# ALU_Adder.net
KiCad netlist of a schematic drawn in Altium Designer
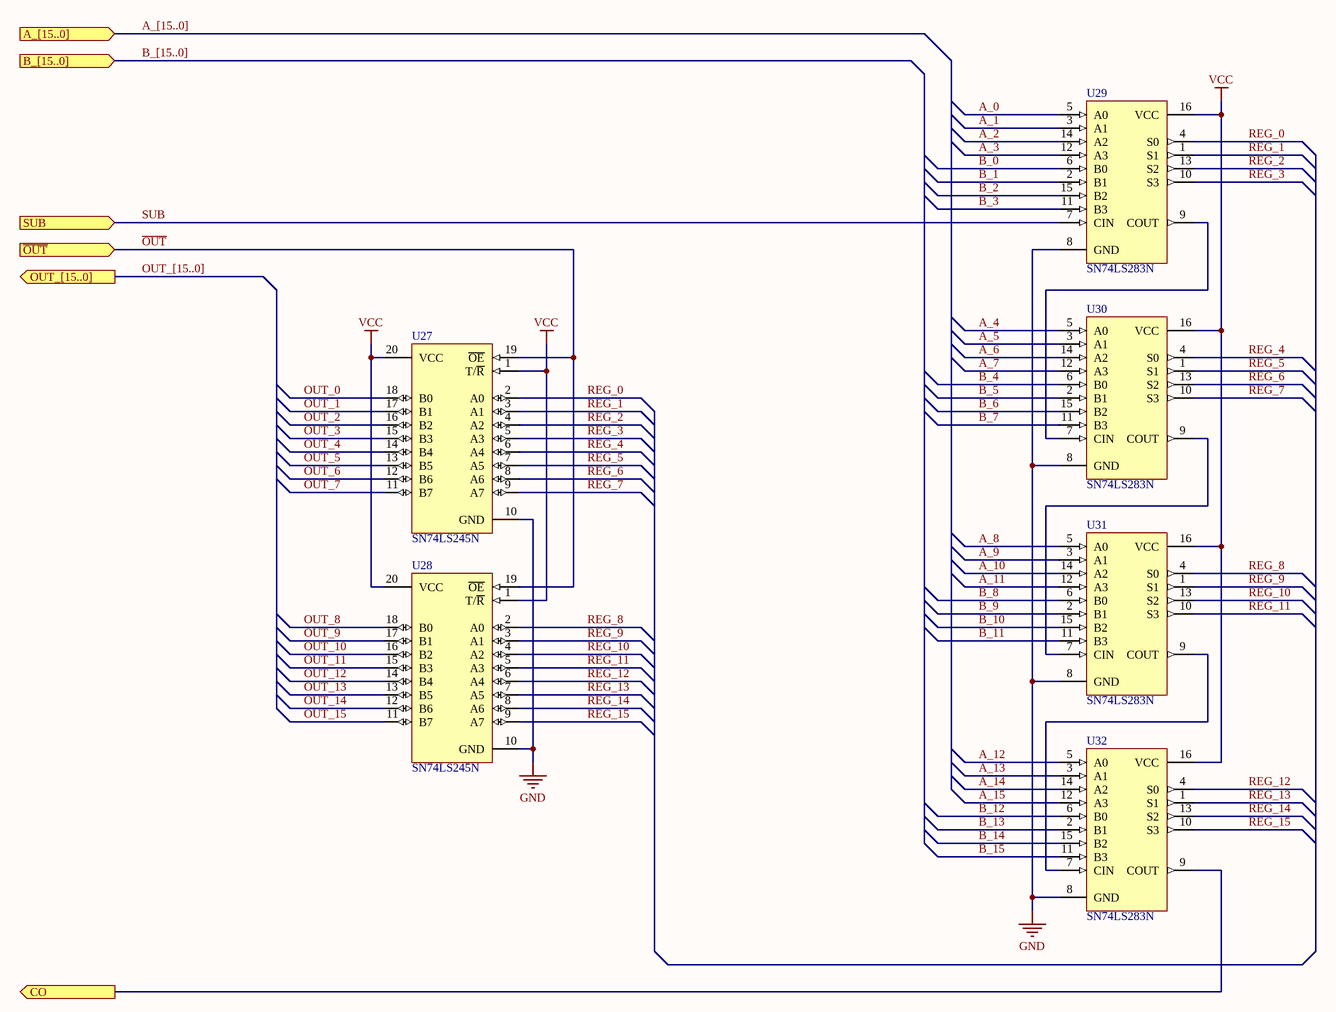
[diagram p0: ALU_Adder.SchDoc]

(export (version "E")
  (design (tool "Eeschema 10.0.6"))
  (components
    (comp (ref "U27")
      (value "SN74LS245N")
      (footprint "N020")
      (description "Octal Bus Transceiver with 3-State Outputs")
      (fields (field (name "PUBLISHER") "Altium Limited"))
      (libsource (lib "TI Interface 8-Bit Line Transceiver") (part "SN74LS245N"))
    )
    (comp (ref "U28")
      (value "SN74LS245N")
      (footprint "N020")
      (description "Octal Bus Transceiver with 3-State Outputs")
      (fields (field (name "PUBLISHER") "Altium Limited"))
      (libsource (lib "TI Interface 8-Bit Line Transceiver") (part "SN74LS245N"))
    )
    (comp (ref "U29")
      (value "SN74LS283N")
      (footprint "W016")
      (description "4-Bit Binary Full Adder with Fast Carry")
      (fields (field (name "PUBLISHER") "Altium Limited"))
      (libsource (lib "TI Logic Arithmetic") (part "SN74LS283N"))
    )
    (comp (ref "U30")
      (value "SN74LS283N")
      (footprint "W016")
      (description "4-Bit Binary Full Adder with Fast Carry")
      (fields (field (name "PUBLISHER") "Altium Limited"))
      (libsource (lib "TI Logic Arithmetic") (part "SN74LS283N"))
    )
    (comp (ref "U31")
      (value "SN74LS283N")
      (footprint "W016")
      (description "4-Bit Binary Full Adder with Fast Carry")
      (fields (field (name "PUBLISHER") "Altium Limited"))
      (libsource (lib "TI Logic Arithmetic") (part "SN74LS283N"))
    )
    (comp (ref "U32")
      (value "SN74LS283N")
      (footprint "W016")
      (description "4-Bit Binary Full Adder with Fast Carry")
      (fields (field (name "PUBLISHER") "Altium Limited"))
      (libsource (lib "TI Logic Arithmetic") (part "SN74LS283N"))
    )
  )
  (nets
    (net (code "1") (name "/A_0") (class "Default")
      (node (ref "U29") (pin "5") (pinfunction "A0_5") (pintype "input"))
    )
    (net (code "2") (name "/A_1") (class "Default")
      (node (ref "U29") (pin "3") (pinfunction "A1_3") (pintype "input"))
    )
    (net (code "3") (name "/A_2") (class "Default")
      (node (ref "U29") (pin "14") (pinfunction "A2_14") (pintype "input"))
    )
    (net (code "4") (name "/A_3") (class "Default")
      (node (ref "U29") (pin "12") (pinfunction "A3_12") (pintype "input"))
    )
    (net (code "5") (name "/A_4") (class "Default")
      (node (ref "U30") (pin "5") (pinfunction "A0_5") (pintype "input"))
    )
    (net (code "6") (name "/A_5") (class "Default")
      (node (ref "U30") (pin "3") (pinfunction "A1_3") (pintype "input"))
    )
    (net (code "7") (name "/A_6") (class "Default")
      (node (ref "U30") (pin "14") (pinfunction "A2_14") (pintype "input"))
    )
    (net (code "8") (name "/A_7") (class "Default")
      (node (ref "U30") (pin "12") (pinfunction "A3_12") (pintype "input"))
    )
    (net (code "9") (name "/A_8") (class "Default")
      (node (ref "U31") (pin "5") (pinfunction "A0_5") (pintype "input"))
    )
    (net (code "10") (name "/A_9") (class "Default")
      (node (ref "U31") (pin "3") (pinfunction "A1_3") (pintype "input"))
    )
    (net (code "11") (name "/A_10") (class "Default")
      (node (ref "U31") (pin "14") (pinfunction "A2_14") (pintype "input"))
    )
    (net (code "12") (name "/A_11") (class "Default")
      (node (ref "U31") (pin "12") (pinfunction "A3_12") (pintype "input"))
    )
    (net (code "13") (name "/A_12") (class "Default")
      (node (ref "U32") (pin "5") (pinfunction "A0_5") (pintype "input"))
    )
    (net (code "14") (name "/A_13") (class "Default")
      (node (ref "U32") (pin "3") (pinfunction "A1_3") (pintype "input"))
    )
    (net (code "15") (name "/A_14") (class "Default")
      (node (ref "U32") (pin "14") (pinfunction "A2_14") (pintype "input"))
    )
    (net (code "16") (name "/A_15") (class "Default")
      (node (ref "U32") (pin "12") (pinfunction "A3_12") (pintype "input"))
    )
    (net (code "18") (name "/B_0") (class "Default")
      (node (ref "U29") (pin "6") (pinfunction "B0_6") (pintype "input"))
    )
    (net (code "19") (name "/B_1") (class "Default")
      (node (ref "U29") (pin "2") (pinfunction "B1_2") (pintype "input"))
    )
    (net (code "20") (name "/B_2") (class "Default")
      (node (ref "U29") (pin "15") (pinfunction "B2_15") (pintype "input"))
    )
    (net (code "21") (name "/B_3") (class "Default")
      (node (ref "U29") (pin "11") (pinfunction "B3_11") (pintype "input"))
    )
    (net (code "22") (name "/B_4") (class "Default")
      (node (ref "U30") (pin "6") (pinfunction "B0_6") (pintype "input"))
    )
    (net (code "23") (name "/B_5") (class "Default")
      (node (ref "U30") (pin "2") (pinfunction "B1_2") (pintype "input"))
    )
    (net (code "24") (name "/B_6") (class "Default")
      (node (ref "U30") (pin "15") (pinfunction "B2_15") (pintype "input"))
    )
    (net (code "25") (name "/B_7") (class "Default")
      (node (ref "U30") (pin "11") (pinfunction "B3_11") (pintype "input"))
    )
    (net (code "26") (name "/B_8") (class "Default")
      (node (ref "U31") (pin "6") (pinfunction "B0_6") (pintype "input"))
    )
    (net (code "27") (name "/B_9") (class "Default")
      (node (ref "U31") (pin "2") (pinfunction "B1_2") (pintype "input"))
    )
    (net (code "28") (name "/B_10") (class "Default")
      (node (ref "U31") (pin "15") (pinfunction "B2_15") (pintype "input"))
    )
    (net (code "29") (name "/B_11") (class "Default")
      (node (ref "U31") (pin "11") (pinfunction "B3_11") (pintype "input"))
    )
    (net (code "30") (name "/B_12") (class "Default")
      (node (ref "U32") (pin "6") (pinfunction "B0_6") (pintype "input"))
    )
    (net (code "31") (name "/B_13") (class "Default")
      (node (ref "U32") (pin "2") (pinfunction "B1_2") (pintype "input"))
    )
    (net (code "32") (name "/B_14") (class "Default")
      (node (ref "U32") (pin "15") (pinfunction "B2_15") (pintype "input"))
    )
    (net (code "33") (name "/B_15") (class "Default")
      (node (ref "U32") (pin "11") (pinfunction "B3_11") (pintype "input"))
    )
    (net (code "35") (name "/CO") (class "Default")
      (node (ref "U32") (pin "9") (pinfunction "COUT_9") (pintype "output"))
    )
    (net (code "36") (name "/OUT_0") (class "Default")
      (node (ref "U27") (pin "18") (pinfunction "B0_18") (pintype "bidirectional"))
    )
    (net (code "37") (name "/OUT_1") (class "Default")
      (node (ref "U27") (pin "17") (pinfunction "B1_17") (pintype "bidirectional"))
    )
    (net (code "38") (name "/OUT_2") (class "Default")
      (node (ref "U27") (pin "16") (pinfunction "B2_16") (pintype "bidirectional"))
    )
    (net (code "39") (name "/OUT_3") (class "Default")
      (node (ref "U27") (pin "15") (pinfunction "B3_15") (pintype "bidirectional"))
    )
    (net (code "40") (name "/OUT_4") (class "Default")
      (node (ref "U27") (pin "14") (pinfunction "B4_14") (pintype "bidirectional"))
    )
    (net (code "41") (name "/OUT_5") (class "Default")
      (node (ref "U27") (pin "13") (pinfunction "B5_13") (pintype "bidirectional"))
    )
    (net (code "42") (name "/OUT_6") (class "Default")
      (node (ref "U27") (pin "12") (pinfunction "B6_12") (pintype "bidirectional"))
    )
    (net (code "43") (name "/OUT_7") (class "Default")
      (node (ref "U27") (pin "11") (pinfunction "B7_11") (pintype "bidirectional"))
    )
    (net (code "44") (name "/OUT_8") (class "Default")
      (node (ref "U28") (pin "18") (pinfunction "B0_18") (pintype "bidirectional"))
    )
    (net (code "45") (name "/OUT_9") (class "Default")
      (node (ref "U28") (pin "17") (pinfunction "B1_17") (pintype "bidirectional"))
    )
    (net (code "46") (name "/OUT_10") (class "Default")
      (node (ref "U28") (pin "16") (pinfunction "B2_16") (pintype "bidirectional"))
    )
    (net (code "47") (name "/OUT_11") (class "Default")
      (node (ref "U28") (pin "15") (pinfunction "B3_15") (pintype "bidirectional"))
    )
    (net (code "48") (name "/OUT_12") (class "Default")
      (node (ref "U28") (pin "14") (pinfunction "B4_14") (pintype "bidirectional"))
    )
    (net (code "49") (name "/OUT_13") (class "Default")
      (node (ref "U28") (pin "13") (pinfunction "B5_13") (pintype "bidirectional"))
    )
    (net (code "50") (name "/OUT_14") (class "Default")
      (node (ref "U28") (pin "12") (pinfunction "B6_12") (pintype "bidirectional"))
    )
    (net (code "51") (name "/OUT_15") (class "Default")
      (node (ref "U28") (pin "11") (pinfunction "B7_11") (pintype "bidirectional"))
    )
    (net (code "53") (name "/REG_0") (class "Default")
      (node (ref "U27") (pin "2") (pinfunction "A0_2") (pintype "bidirectional"))
      (node (ref "U29") (pin "4") (pinfunction "S0_4") (pintype "output"))
    )
    (net (code "54") (name "/REG_1") (class "Default")
      (node (ref "U27") (pin "3") (pinfunction "A1_3") (pintype "bidirectional"))
      (node (ref "U29") (pin "1") (pinfunction "S1_1") (pintype "output"))
    )
    (net (code "55") (name "/REG_2") (class "Default")
      (node (ref "U27") (pin "4") (pinfunction "A2_4") (pintype "bidirectional"))
      (node (ref "U29") (pin "13") (pinfunction "S2_13") (pintype "output"))
    )
    (net (code "56") (name "/REG_3") (class "Default")
      (node (ref "U27") (pin "5") (pinfunction "A3_5") (pintype "bidirectional"))
      (node (ref "U29") (pin "10") (pinfunction "S3_10") (pintype "output"))
    )
    (net (code "57") (name "/REG_4") (class "Default")
      (node (ref "U27") (pin "6") (pinfunction "A4_6") (pintype "bidirectional"))
      (node (ref "U30") (pin "4") (pinfunction "S0_4") (pintype "output"))
    )
    (net (code "58") (name "/REG_5") (class "Default")
      (node (ref "U27") (pin "7") (pinfunction "A5_7") (pintype "bidirectional"))
      (node (ref "U30") (pin "1") (pinfunction "S1_1") (pintype "output"))
    )
    (net (code "59") (name "/REG_6") (class "Default")
      (node (ref "U27") (pin "8") (pinfunction "A6_8") (pintype "bidirectional"))
      (node (ref "U30") (pin "13") (pinfunction "S2_13") (pintype "output"))
    )
    (net (code "60") (name "/REG_7") (class "Default")
      (node (ref "U27") (pin "9") (pinfunction "A7_9") (pintype "bidirectional"))
      (node (ref "U30") (pin "10") (pinfunction "S3_10") (pintype "output"))
    )
    (net (code "61") (name "/REG_8") (class "Default")
      (node (ref "U28") (pin "2") (pinfunction "A0_2") (pintype "bidirectional"))
      (node (ref "U31") (pin "4") (pinfunction "S0_4") (pintype "output"))
    )
    (net (code "62") (name "/REG_9") (class "Default")
      (node (ref "U28") (pin "3") (pinfunction "A1_3") (pintype "bidirectional"))
      (node (ref "U31") (pin "1") (pinfunction "S1_1") (pintype "output"))
    )
    (net (code "63") (name "/REG_10") (class "Default")
      (node (ref "U28") (pin "4") (pinfunction "A2_4") (pintype "bidirectional"))
      (node (ref "U31") (pin "13") (pinfunction "S2_13") (pintype "output"))
    )
    (net (code "64") (name "/REG_11") (class "Default")
      (node (ref "U28") (pin "5") (pinfunction "A3_5") (pintype "bidirectional"))
      (node (ref "U31") (pin "10") (pinfunction "S3_10") (pintype "output"))
    )
    (net (code "65") (name "/REG_12") (class "Default")
      (node (ref "U28") (pin "6") (pinfunction "A4_6") (pintype "bidirectional"))
      (node (ref "U32") (pin "4") (pinfunction "S0_4") (pintype "output"))
    )
    (net (code "66") (name "/REG_13") (class "Default")
      (node (ref "U28") (pin "7") (pinfunction "A5_7") (pintype "bidirectional"))
      (node (ref "U32") (pin "1") (pinfunction "S1_1") (pintype "output"))
    )
    (net (code "67") (name "/REG_14") (class "Default")
      (node (ref "U28") (pin "8") (pinfunction "A6_8") (pintype "bidirectional"))
      (node (ref "U32") (pin "13") (pinfunction "S2_13") (pintype "output"))
    )
    (net (code "68") (name "/REG_15") (class "Default")
      (node (ref "U28") (pin "9") (pinfunction "A7_9") (pintype "bidirectional"))
      (node (ref "U32") (pin "10") (pinfunction "S3_10") (pintype "output"))
    )
    (net (code "69") (name "/SUB") (class "Default")
      (node (ref "U29") (pin "7") (pinfunction "CIN_7") (pintype "input"))
    )
    (net (code "70") (name "/~{OUT}") (class "Default")
      (node (ref "U27") (pin "19") (pinfunction "~{OE}_19") (pintype "input"))
      (node (ref "U28") (pin "19") (pinfunction "~{OE}_19") (pintype "input"))
    )
    (net (code "71") (name "GND") (class "Default")
      (node (ref "U27") (pin "10") (pinfunction "GND_10") (pintype "power_in"))
      (node (ref "U28") (pin "10") (pinfunction "GND_10") (pintype "power_in"))
      (node (ref "U29") (pin "8") (pinfunction "GND_8") (pintype "power_in"))
      (node (ref "U30") (pin "8") (pinfunction "GND_8") (pintype "power_in"))
      (node (ref "U31") (pin "8") (pinfunction "GND_8") (pintype "power_in"))
      (node (ref "U32") (pin "8") (pinfunction "GND_8") (pintype "power_in"))
    )
    (net (code "72") (name "Net-(U29-COUT)") (class "Default")
      (node (ref "U29") (pin "9") (pinfunction "COUT_9") (pintype "output"))
      (node (ref "U30") (pin "7") (pinfunction "CIN_7") (pintype "input"))
    )
    (net (code "73") (name "Net-(U30-COUT)") (class "Default")
      (node (ref "U30") (pin "9") (pinfunction "COUT_9") (pintype "output"))
      (node (ref "U31") (pin "7") (pinfunction "CIN_7") (pintype "input"))
    )
    (net (code "74") (name "Net-(U31-COUT)") (class "Default")
      (node (ref "U31") (pin "9") (pinfunction "COUT_9") (pintype "output"))
      (node (ref "U32") (pin "7") (pinfunction "CIN_7") (pintype "input"))
    )
    (net (code "75") (name "VCC") (class "Default")
      (node (ref "U27") (pin "1") (pinfunction "T/~{R}_1") (pintype "input"))
      (node (ref "U27") (pin "20") (pinfunction "VCC_20") (pintype "power_in"))
      (node (ref "U28") (pin "1") (pinfunction "T/~{R}_1") (pintype "input"))
      (node (ref "U28") (pin "20") (pinfunction "VCC_20") (pintype "power_in"))
      (node (ref "U29") (pin "16") (pinfunction "VCC_16") (pintype "power_in"))
      (node (ref "U30") (pin "16") (pinfunction "VCC_16") (pintype "power_in"))
      (node (ref "U31") (pin "16") (pinfunction "VCC_16") (pintype "power_in"))
      (node (ref "U32") (pin "16") (pinfunction "VCC_16") (pintype "power_in"))
    )
  )
)
